# Phase_3_1_Form_Factor_1.net
KiCad netlist of a schematic drawn in EAGLE
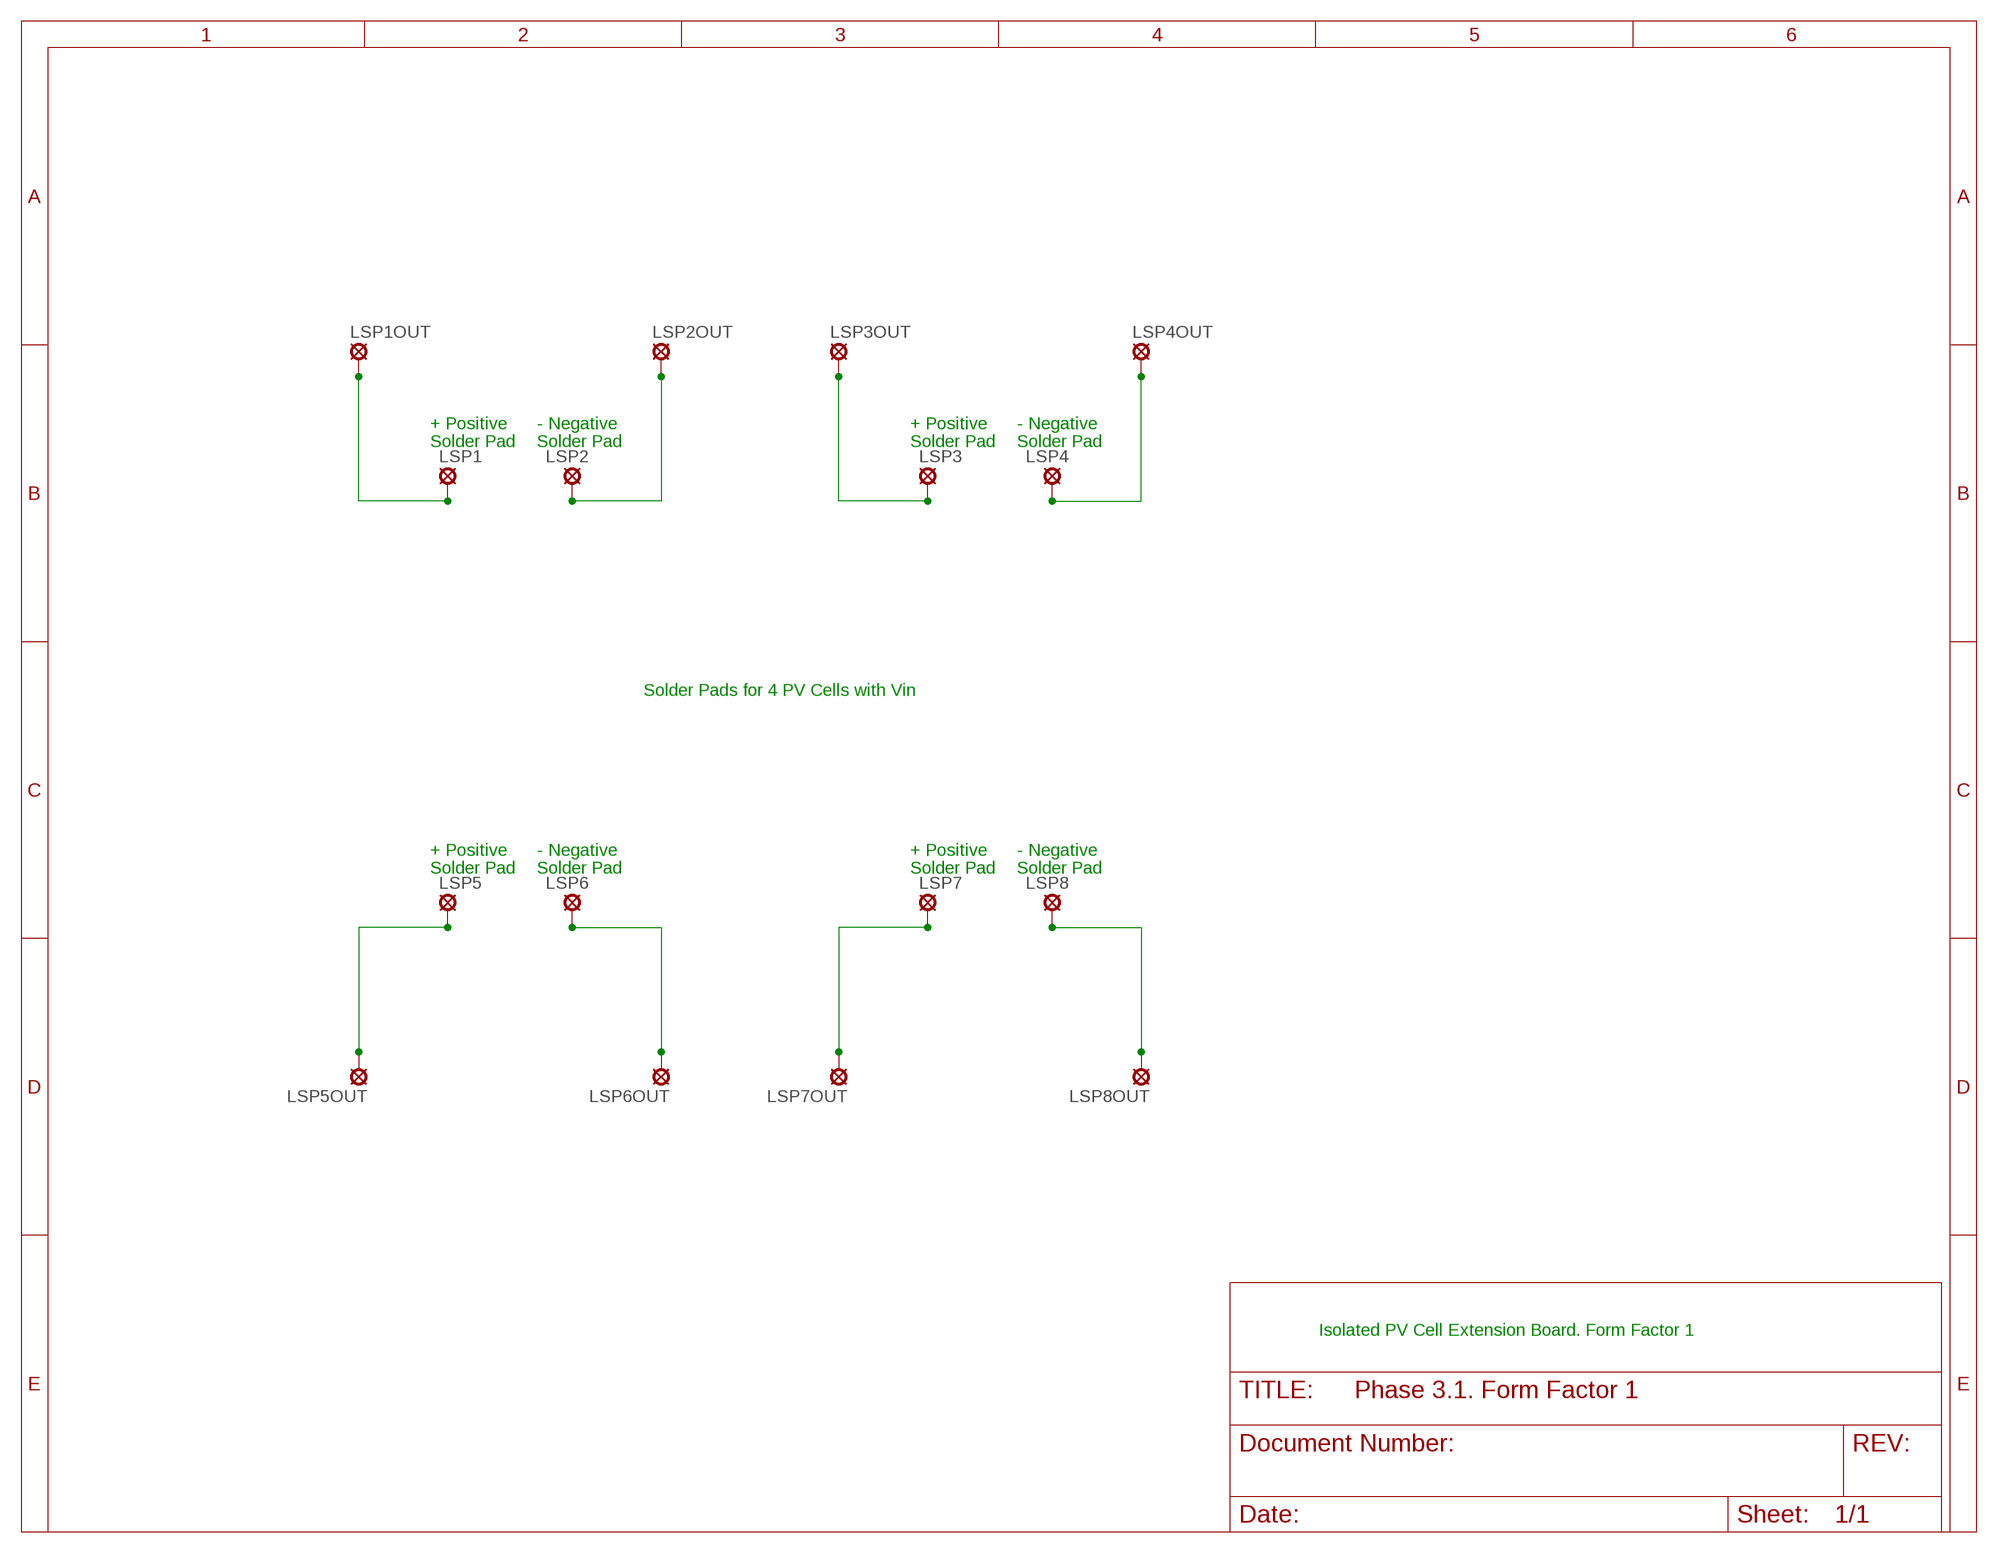
[diagram p0: schematic, sheet 1]

(export (version "E")
  (design (tool "Eeschema 10.0.6"))
  (components
    (comp (ref "LSP1")
      (value "LSP10")
      (footprint "eagle-import:LSP10")
      (libsource (lib "eagle-import") (part "LSP10"))
    )
    (comp (ref "LSP1OUT")
      (value "LSP10")
      (footprint "eagle-import:LSP10")
      (libsource (lib "eagle-import") (part "LSP10"))
    )
    (comp (ref "LSP2")
      (value "LSP10")
      (footprint "eagle-import:LSP10")
      (libsource (lib "eagle-import") (part "LSP10"))
    )
    (comp (ref "LSP2OUT")
      (value "LSP10")
      (footprint "eagle-import:LSP10")
      (libsource (lib "eagle-import") (part "LSP10"))
    )
    (comp (ref "LSP3")
      (value "LSP10")
      (footprint "eagle-import:LSP10")
      (libsource (lib "eagle-import") (part "LSP10"))
    )
    (comp (ref "LSP3OUT")
      (value "LSP10")
      (footprint "eagle-import:LSP10")
      (libsource (lib "eagle-import") (part "LSP10"))
    )
    (comp (ref "LSP4")
      (value "LSP10")
      (footprint "eagle-import:LSP10")
      (libsource (lib "eagle-import") (part "LSP10"))
    )
    (comp (ref "LSP4OUT")
      (value "LSP10")
      (footprint "eagle-import:LSP10")
      (libsource (lib "eagle-import") (part "LSP10"))
    )
    (comp (ref "LSP5")
      (value "LSP10")
      (footprint "eagle-import:LSP10")
      (libsource (lib "eagle-import") (part "LSP10"))
    )
    (comp (ref "LSP5OUT")
      (value "LSP10")
      (footprint "eagle-import:LSP10")
      (libsource (lib "eagle-import") (part "LSP10"))
    )
    (comp (ref "LSP6")
      (value "LSP10")
      (footprint "eagle-import:LSP10")
      (libsource (lib "eagle-import") (part "LSP10"))
    )
    (comp (ref "LSP6OUT")
      (value "LSP10")
      (footprint "eagle-import:LSP10")
      (libsource (lib "eagle-import") (part "LSP10"))
    )
    (comp (ref "LSP7")
      (value "LSP10")
      (footprint "eagle-import:LSP10")
      (libsource (lib "eagle-import") (part "LSP10"))
    )
    (comp (ref "LSP7OUT")
      (value "LSP10")
      (footprint "eagle-import:LSP10")
      (libsource (lib "eagle-import") (part "LSP10"))
    )
    (comp (ref "LSP8")
      (value "LSP10")
      (footprint "eagle-import:LSP10")
      (libsource (lib "eagle-import") (part "LSP10"))
    )
    (comp (ref "LSP8OUT")
      (value "LSP10")
      (footprint "eagle-import:LSP10")
      (libsource (lib "eagle-import") (part "LSP10"))
    )
  )
  (nets
    (net (code "1") (name "Net-(LSP1-PadMP)") (class "Default")
      (node (ref "LSP1") (pin "MP") (pinfunction "MP_MP") (pintype "passive"))
      (node (ref "LSP1OUT") (pin "MP") (pinfunction "MP_MP") (pintype "passive"))
    )
    (net (code "2") (name "Net-(LSP2-PadMP)") (class "Default")
      (node (ref "LSP2") (pin "MP") (pinfunction "MP_MP") (pintype "passive"))
      (node (ref "LSP2OUT") (pin "MP") (pinfunction "MP_MP") (pintype "passive"))
    )
    (net (code "3") (name "Net-(LSP3-PadMP)") (class "Default")
      (node (ref "LSP3") (pin "MP") (pinfunction "MP_MP") (pintype "passive"))
      (node (ref "LSP3OUT") (pin "MP") (pinfunction "MP_MP") (pintype "passive"))
    )
    (net (code "4") (name "Net-(LSP4-PadMP)") (class "Default")
      (node (ref "LSP4") (pin "MP") (pinfunction "MP_MP") (pintype "passive"))
      (node (ref "LSP4OUT") (pin "MP") (pinfunction "MP_MP") (pintype "passive"))
    )
    (net (code "5") (name "Net-(LSP5-PadMP)") (class "Default")
      (node (ref "LSP5") (pin "MP") (pinfunction "MP_MP") (pintype "passive"))
      (node (ref "LSP5OUT") (pin "MP") (pinfunction "MP_MP") (pintype "passive"))
    )
    (net (code "6") (name "Net-(LSP6-PadMP)") (class "Default")
      (node (ref "LSP6") (pin "MP") (pinfunction "MP_MP") (pintype "passive"))
      (node (ref "LSP6OUT") (pin "MP") (pinfunction "MP_MP") (pintype "passive"))
    )
    (net (code "7") (name "Net-(LSP7-PadMP)") (class "Default")
      (node (ref "LSP7") (pin "MP") (pinfunction "MP_MP") (pintype "passive"))
      (node (ref "LSP7OUT") (pin "MP") (pinfunction "MP_MP") (pintype "passive"))
    )
    (net (code "8") (name "Net-(LSP8-PadMP)") (class "Default")
      (node (ref "LSP8") (pin "MP") (pinfunction "MP_MP") (pintype "passive"))
      (node (ref "LSP8OUT") (pin "MP") (pinfunction "MP_MP") (pintype "passive"))
    )
  )
)
